# LAN_RJ45.net
KiCad netlist of a schematic drawn in Altium Designer
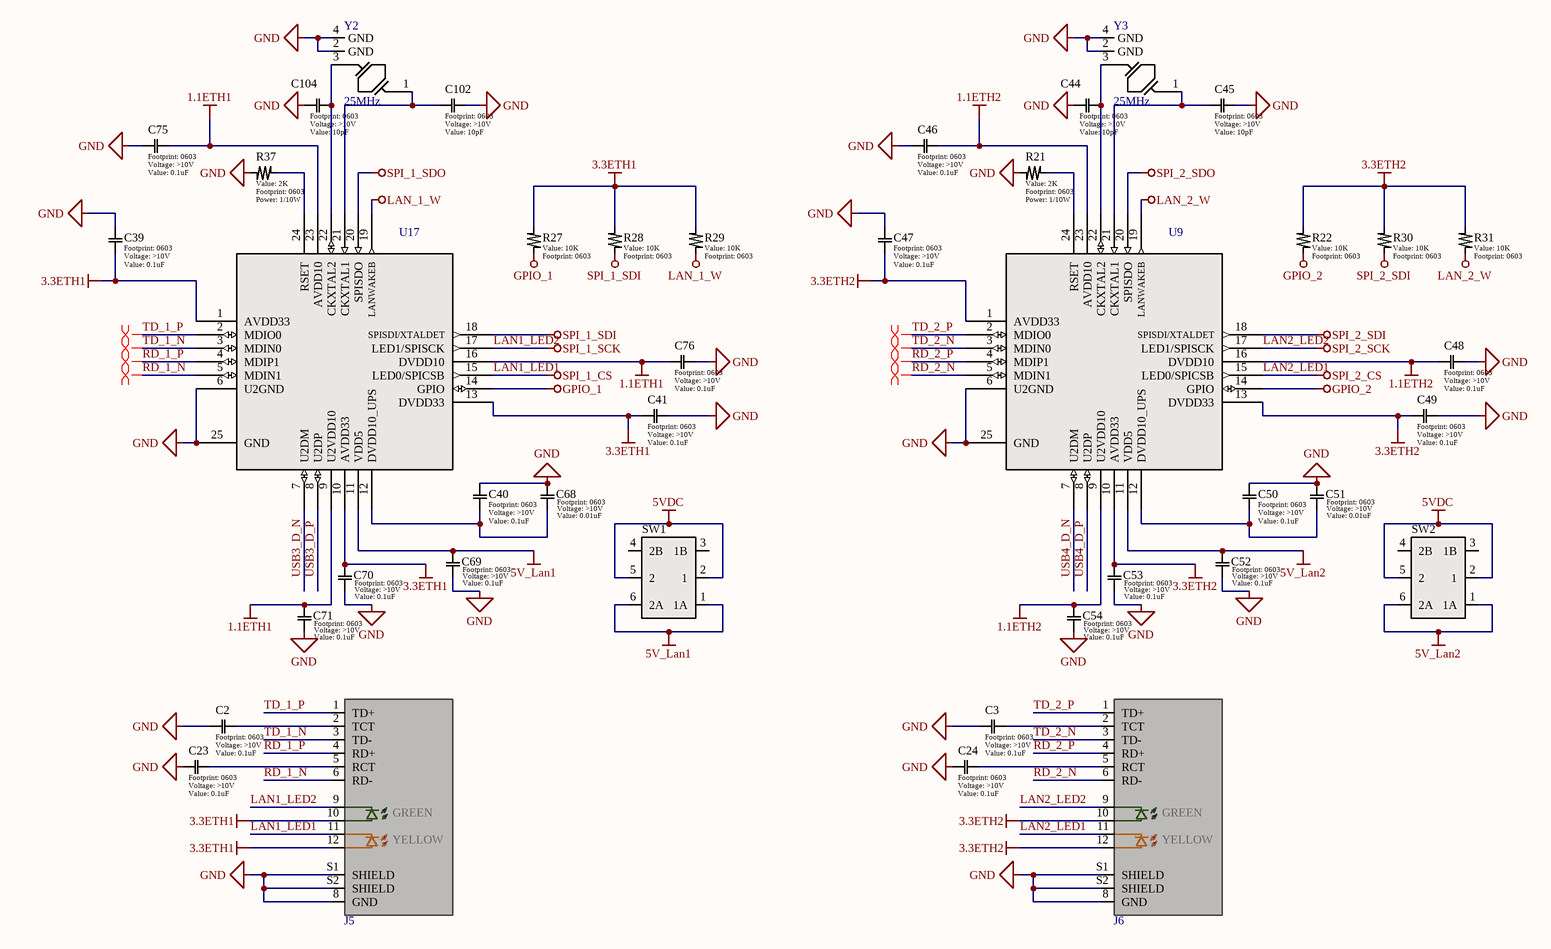
[diagram p0: LAN_RJ45.SchDoc]

(export (version "E")
  (design (tool "Eeschema 10.0.6"))
  (components
    (comp (ref "C2")
      (value "0.1uF")
      (footprint "0603")
      (fields
        (field (name "VOLTAGE") ">10V")
        (field (name "TOLERANCE") "10%")
        (field (name "Comment") "Generic Capacitor")
      )
      (libsource (lib "Capacitors") (part "Generic Capacitor"))
    )
    (comp (ref "C3")
      (value "0.1uF")
      (footprint "0603")
      (fields
        (field (name "VOLTAGE") ">10V")
        (field (name "TOLERANCE") "10%")
        (field (name "Comment") "Generic Capacitor")
      )
      (libsource (lib "Capacitors") (part "Generic Capacitor"))
    )
    (comp (ref "C23")
      (value "0.1uF")
      (footprint "0603")
      (fields
        (field (name "VOLTAGE") ">10V")
        (field (name "TOLERANCE") "10%")
        (field (name "Comment") "Generic Capacitor")
      )
      (libsource (lib "Capacitors") (part "Generic Capacitor"))
    )
    (comp (ref "C24")
      (value "0.1uF")
      (footprint "0603")
      (fields
        (field (name "VOLTAGE") ">10V")
        (field (name "TOLERANCE") "10%")
        (field (name "Comment") "Generic Capacitor")
      )
      (libsource (lib "Capacitors") (part "Generic Capacitor"))
    )
    (comp (ref "C39")
      (value "0.1uF")
      (footprint "0603")
      (fields
        (field (name "VOLTAGE") ">10V")
        (field (name "TOLERANCE") "10%")
        (field (name "Comment") "Generic Capacitor")
      )
      (libsource (lib "Capacitors") (part "Generic Capacitor"))
    )
    (comp (ref "C40")
      (value "0.1uF")
      (footprint "0603")
      (fields
        (field (name "VOLTAGE") ">10V")
        (field (name "TOLERANCE") "10%")
        (field (name "Comment") "Generic Capacitor")
      )
      (libsource (lib "Capacitors") (part "Generic Capacitor"))
    )
    (comp (ref "C41")
      (value "0.1uF")
      (footprint "0603")
      (fields
        (field (name "VOLTAGE") ">10V")
        (field (name "TOLERANCE") "10%")
        (field (name "Comment") "Generic Capacitor")
      )
      (libsource (lib "Capacitors") (part "Generic Capacitor"))
    )
    (comp (ref "C44")
      (value "10pF")
      (footprint "0603")
      (fields
        (field (name "VOLTAGE") ">10V")
        (field (name "TOLERANCE") "10%")
        (field (name "Comment") "Generic Capacitor")
      )
      (libsource (lib "Capacitors") (part "Generic Capacitor"))
    )
    (comp (ref "C45")
      (value "10pF")
      (footprint "0603")
      (fields
        (field (name "VOLTAGE") ">10V")
        (field (name "TOLERANCE") "10%")
        (field (name "Comment") "Generic Capacitor")
      )
      (libsource (lib "Capacitors") (part "Generic Capacitor"))
    )
    (comp (ref "C46")
      (value "0.1uF")
      (footprint "0603")
      (fields
        (field (name "VOLTAGE") ">10V")
        (field (name "TOLERANCE") "10%")
        (field (name "Comment") "Generic Capacitor")
      )
      (libsource (lib "Capacitors") (part "Generic Capacitor"))
    )
    (comp (ref "C47")
      (value "0.1uF")
      (footprint "0603")
      (fields
        (field (name "VOLTAGE") ">10V")
        (field (name "TOLERANCE") "10%")
        (field (name "Comment") "Generic Capacitor")
      )
      (libsource (lib "Capacitors") (part "Generic Capacitor"))
    )
    (comp (ref "C48")
      (value "0.1uF")
      (footprint "0603")
      (fields
        (field (name "VOLTAGE") ">10V")
        (field (name "TOLERANCE") "10%")
        (field (name "Comment") "Generic Capacitor")
      )
      (libsource (lib "Capacitors") (part "Generic Capacitor"))
    )
    (comp (ref "C49")
      (value "0.1uF")
      (footprint "0603")
      (fields
        (field (name "VOLTAGE") ">10V")
        (field (name "TOLERANCE") "10%")
        (field (name "Comment") "Generic Capacitor")
      )
      (libsource (lib "Capacitors") (part "Generic Capacitor"))
    )
    (comp (ref "C50")
      (value "0.1uF")
      (footprint "0603")
      (fields
        (field (name "VOLTAGE") ">10V")
        (field (name "TOLERANCE") "10%")
        (field (name "Comment") "Generic Capacitor")
      )
      (libsource (lib "Capacitors") (part "Generic Capacitor"))
    )
    (comp (ref "C51")
      (value "0.01uF")
      (footprint "0603")
      (fields
        (field (name "VOLTAGE") ">10V")
        (field (name "TOLERANCE") "10%")
        (field (name "Comment") "Generic Capacitor")
      )
      (libsource (lib "Capacitors") (part "Generic Capacitor"))
    )
    (comp (ref "C52")
      (value "0.1uF")
      (footprint "0603")
      (fields
        (field (name "VOLTAGE") ">10V")
        (field (name "TOLERANCE") "10%")
        (field (name "Comment") "Generic Capacitor")
      )
      (libsource (lib "Capacitors") (part "Generic Capacitor"))
    )
    (comp (ref "C53")
      (value "0.1uF")
      (footprint "0603")
      (fields
        (field (name "VOLTAGE") ">10V")
        (field (name "TOLERANCE") "10%")
        (field (name "Comment") "Generic Capacitor")
      )
      (libsource (lib "Capacitors") (part "Generic Capacitor"))
    )
    (comp (ref "C54")
      (value "0.1uF")
      (footprint "0603")
      (fields
        (field (name "VOLTAGE") ">10V")
        (field (name "TOLERANCE") "10%")
        (field (name "Comment") "Generic Capacitor")
      )
      (libsource (lib "Capacitors") (part "Generic Capacitor"))
    )
    (comp (ref "C68")
      (value "0.01uF")
      (footprint "0603")
      (fields
        (field (name "VOLTAGE") ">10V")
        (field (name "TOLERANCE") "10%")
        (field (name "Comment") "Generic Capacitor")
      )
      (libsource (lib "Capacitors") (part "Generic Capacitor"))
    )
    (comp (ref "C69")
      (value "0.1uF")
      (footprint "0603")
      (fields
        (field (name "VOLTAGE") ">10V")
        (field (name "TOLERANCE") "10%")
        (field (name "Comment") "Generic Capacitor")
      )
      (libsource (lib "Capacitors") (part "Generic Capacitor"))
    )
    (comp (ref "C70")
      (value "0.1uF")
      (footprint "0603")
      (fields
        (field (name "VOLTAGE") ">10V")
        (field (name "TOLERANCE") "10%")
        (field (name "Comment") "Generic Capacitor")
      )
      (libsource (lib "Capacitors") (part "Generic Capacitor"))
    )
    (comp (ref "C71")
      (value "0.1uF")
      (footprint "0603")
      (fields
        (field (name "VOLTAGE") ">10V")
        (field (name "TOLERANCE") "10%")
        (field (name "Comment") "Generic Capacitor")
      )
      (libsource (lib "Capacitors") (part "Generic Capacitor"))
    )
    (comp (ref "C75")
      (value "0.1uF")
      (footprint "0603")
      (fields
        (field (name "VOLTAGE") ">10V")
        (field (name "TOLERANCE") "10%")
        (field (name "Comment") "Generic Capacitor")
      )
      (libsource (lib "Capacitors") (part "Generic Capacitor"))
    )
    (comp (ref "C76")
      (value "0.1uF")
      (footprint "0603")
      (fields
        (field (name "VOLTAGE") ">10V")
        (field (name "TOLERANCE") "10%")
        (field (name "Comment") "Generic Capacitor")
      )
      (libsource (lib "Capacitors") (part "Generic Capacitor"))
    )
    (comp (ref "C102")
      (value "10pF")
      (footprint "0603")
      (fields
        (field (name "VOLTAGE") ">10V")
        (field (name "TOLERANCE") "10%")
        (field (name "Comment") "Generic Capacitor")
      )
      (libsource (lib "Capacitors") (part "Generic Capacitor"))
    )
    (comp (ref "C104")
      (value "10pF")
      (footprint "0603")
      (fields
        (field (name "VOLTAGE") ">10V")
        (field (name "TOLERANCE") "10%")
        (field (name "Comment") "Generic Capacitor")
      )
      (libsource (lib "Capacitors") (part "Generic Capacitor"))
    )
    (comp (ref "J5")
      (value "V-RJ45-100")
      (footprint "BEL_SI-46001-F")
      (description "Conn RJ-45 F 8 POS 2.54mm Solder ST Thru-Hole 12 Terminal 1 Port")
      (fields (field (name "MF") "Bel Magnetic Solutions") (field (name "MP") "SI-46001-F"))
      (libsource (lib "Connectors") (part "SI-46001-F"))
    )
    (comp (ref "J6")
      (value "V-RJ45-100")
      (footprint "BEL_SI-46001-F")
      (description "Conn RJ-45 F 8 POS 2.54mm Solder ST Thru-Hole 12 Terminal 1 Port")
      (fields (field (name "MF") "Bel Magnetic Solutions") (field (name "MP") "SI-46001-F"))
      (libsource (lib "Connectors") (part "SI-46001-F"))
    )
    (comp (ref "R21")
      (value "2K")
      (footprint "0603")
      (fields
        (field (name "TOLERANCE") "1%")
        (field (name "POWER") "1/10W")
        (field (name "Comment") "Generic Resistor")
      )
      (libsource (lib "Resistors") (part "Generic Resistor"))
    )
    (comp (ref "R22")
      (value "10K")
      (footprint "0603")
      (fields
        (field (name "TOLERANCE") "1%")
        (field (name "POWER") "1/10W")
        (field (name "Comment") "Generic Resistor")
      )
      (libsource (lib "Resistors") (part "Generic Resistor"))
    )
    (comp (ref "R27")
      (value "10K")
      (footprint "0603")
      (fields
        (field (name "TOLERANCE") "1%")
        (field (name "POWER") "1/10W")
        (field (name "Comment") "Generic Resistor")
      )
      (libsource (lib "Resistors") (part "Generic Resistor"))
    )
    (comp (ref "R28")
      (value "10K")
      (footprint "0603")
      (fields
        (field (name "TOLERANCE") "1%")
        (field (name "POWER") "1/10W")
        (field (name "Comment") "Generic Resistor")
      )
      (libsource (lib "Resistors") (part "Generic Resistor"))
    )
    (comp (ref "R29")
      (value "10K")
      (footprint "0603")
      (fields
        (field (name "TOLERANCE") "1%")
        (field (name "POWER") "1/10W")
        (field (name "Comment") "Generic Resistor")
      )
      (libsource (lib "Resistors") (part "Generic Resistor"))
    )
    (comp (ref "R30")
      (value "10K")
      (footprint "0603")
      (fields
        (field (name "TOLERANCE") "1%")
        (field (name "POWER") "1/10W")
        (field (name "Comment") "Generic Resistor")
      )
      (libsource (lib "Resistors") (part "Generic Resistor"))
    )
    (comp (ref "R31")
      (value "10K")
      (footprint "0603")
      (fields
        (field (name "TOLERANCE") "1%")
        (field (name "POWER") "1/10W")
        (field (name "Comment") "Generic Resistor")
      )
      (libsource (lib "Resistors") (part "Generic Resistor"))
    )
    (comp (ref "R37")
      (value "2K")
      (footprint "0603")
      (fields
        (field (name "TOLERANCE") "1%")
        (field (name "POWER") "1/10W")
        (field (name "Comment") "Generic Resistor")
      )
      (libsource (lib "Resistors") (part "Generic Resistor"))
    )
    (comp (ref "SW1")
      (value "~")
      (footprint "SMD-DPDT-SW")
      (description "Brick nogging DPDT Black SMD Slide Switch")
      (libsource (lib "Switches") (part "MS-22D17-G2"))
    )
    (comp (ref "SW2")
      (value "~")
      (footprint "SMD-DPDT-SW")
      (description "Brick nogging DPDT Black SMD Slide Switch")
      (libsource (lib "Switches") (part "MS-22D17-G2"))
    )
    (comp (ref "U9")
      (value "10/100 USB LAN")
      (footprint "RTL8152B-VB-CG")
      (libsource (lib "Misc ICs") (part "RTL8152B-VB-CG"))
    )
    (comp (ref "U17")
      (value "10/100 USB LAN")
      (footprint "RTL8152B-VB-CG")
      (libsource (lib "Misc ICs") (part "RTL8152B-VB-CG"))
    )
    (comp (ref "Y2")
      (value "25MHz")
      (footprint "SMD3225-4P")
      (description "25 MHz ±30ppm Crystal 10pF 60 Ohms 4-SMD, No Lead\r\nSMD3225-4P")
      (fields
        (field (name "MANUFACTURER") "Abracon")
        (field (name "MANUFACTURER PART NUMBER") "ABM8G-25.000MHZ-B4Y-T")
      )
      (libsource (lib "Clock ICs") (part "ABM8G-25.000MHZ-B4Y-T"))
    )
    (comp (ref "Y3")
      (value "25MHz")
      (footprint "SMD3225-4P")
      (description "25 MHz ±30ppm Crystal 10pF 60 Ohms 4-SMD, No Lead\r\nSMD3225-4P")
      (fields
        (field (name "MANUFACTURER") "Abracon")
        (field (name "MANUFACTURER PART NUMBER") "ABM8G-25.000MHZ-B4Y-T")
      )
      (libsource (lib "Clock ICs") (part "ABM8G-25.000MHZ-B4Y-T"))
    )
  )
  (nets
    (net (code "1") (name "/RD_1_N") (class "Default")
      (node (ref "J5") (pin "6") (pinfunction "RD-_6") (pintype "passive"))
      (node (ref "U17") (pin "5") (pinfunction "MDIN1_5") (pintype "bidirectional"))
    )
    (net (code "2") (name "/RD_1_P") (class "Default")
      (node (ref "J5") (pin "4") (pinfunction "RD+_4") (pintype "passive"))
      (node (ref "U17") (pin "4") (pinfunction "MDIP1_4") (pintype "bidirectional"))
    )
    (net (code "3") (name "/RD_2_N") (class "Default")
      (node (ref "J6") (pin "6") (pinfunction "RD-_6") (pintype "passive"))
      (node (ref "U9") (pin "5") (pinfunction "MDIN1_5") (pintype "bidirectional"))
    )
    (net (code "4") (name "/RD_2_P") (class "Default")
      (node (ref "J6") (pin "4") (pinfunction "RD+_4") (pintype "passive"))
      (node (ref "U9") (pin "4") (pinfunction "MDIP1_4") (pintype "bidirectional"))
    )
    (net (code "5") (name "/TD_1_N") (class "Default")
      (node (ref "J5") (pin "3") (pinfunction "TD-_3") (pintype "passive"))
      (node (ref "U17") (pin "3") (pinfunction "MDIN0_3") (pintype "bidirectional"))
    )
    (net (code "6") (name "/TD_1_P") (class "Default")
      (node (ref "J5") (pin "1") (pinfunction "TD+_1") (pintype "passive"))
      (node (ref "U17") (pin "2") (pinfunction "MDIO0_2") (pintype "bidirectional"))
    )
    (net (code "7") (name "/TD_2_N") (class "Default")
      (node (ref "J6") (pin "3") (pinfunction "TD-_3") (pintype "passive"))
      (node (ref "U9") (pin "3") (pinfunction "MDIN0_3") (pintype "bidirectional"))
    )
    (net (code "8") (name "/TD_2_P") (class "Default")
      (node (ref "J6") (pin "1") (pinfunction "TD+_1") (pintype "passive"))
      (node (ref "U9") (pin "2") (pinfunction "MDIO0_2") (pintype "bidirectional"))
    )
    (net (code "9") (name "/USB3_D_N") (class "Default")
      (node (ref "U17") (pin "7") (pinfunction "U2DM_7") (pintype "bidirectional"))
    )
    (net (code "10") (name "/USB3_D_P") (class "Default")
      (node (ref "U17") (pin "8") (pinfunction "U2DP_8") (pintype "bidirectional"))
    )
    (net (code "11") (name "/USB4_D_N") (class "Default")
      (node (ref "U9") (pin "7") (pinfunction "U2DM_7") (pintype "bidirectional"))
    )
    (net (code "12") (name "/USB4_D_P") (class "Default")
      (node (ref "U9") (pin "8") (pinfunction "U2DP_8") (pintype "bidirectional"))
    )
    (net (code "13") (name "1.1ETH1") (class "Default")
      (node (ref "C71") (pin "1") (pinfunction "1_1") (pintype "passive"))
      (node (ref "C75") (pin "1") (pinfunction "1_1") (pintype "passive"))
      (node (ref "C76") (pin "2") (pinfunction "2_2") (pintype "passive"))
      (node (ref "U17") (pin "16") (pinfunction "DVDD10_16") (pintype "power_in"))
      (node (ref "U17") (pin "23") (pinfunction "AVDD10_23") (pintype "power_in"))
      (node (ref "U17") (pin "9") (pinfunction "U2VDD10_9") (pintype "power_in"))
    )
    (net (code "14") (name "1.1ETH2") (class "Default")
      (node (ref "C46") (pin "1") (pinfunction "1_1") (pintype "passive"))
      (node (ref "C48") (pin "2") (pinfunction "2_2") (pintype "passive"))
      (node (ref "C54") (pin "1") (pinfunction "1_1") (pintype "passive"))
      (node (ref "U9") (pin "16") (pinfunction "DVDD10_16") (pintype "power_in"))
      (node (ref "U9") (pin "23") (pinfunction "AVDD10_23") (pintype "power_in"))
      (node (ref "U9") (pin "9") (pinfunction "U2VDD10_9") (pintype "power_in"))
    )
    (net (code "15") (name "3.3ETH1") (class "Default")
      (node (ref "C39") (pin "1") (pinfunction "1_1") (pintype "passive"))
      (node (ref "C41") (pin "2") (pinfunction "2_2") (pintype "passive"))
      (node (ref "C70") (pin "1") (pinfunction "1_1") (pintype "passive"))
      (node (ref "J5") (pin "10") (pinfunction "GA_10") (pintype "passive"))
      (node (ref "J5") (pin "12") (pinfunction "YA_12") (pintype "passive"))
      (node (ref "R27") (pin "1") (pinfunction "1_1") (pintype "passive"))
      (node (ref "R28") (pin "1") (pinfunction "1_1") (pintype "passive"))
      (node (ref "R29") (pin "1") (pinfunction "1_1") (pintype "passive"))
      (node (ref "U17") (pin "1") (pinfunction "AVDD33_1") (pintype "power_in"))
      (node (ref "U17") (pin "10") (pinfunction "AVDD33_10") (pintype "power_in"))
      (node (ref "U17") (pin "13") (pinfunction "DVDD33_13") (pintype "power_in"))
    )
    (net (code "16") (name "3.3ETH2") (class "Default")
      (node (ref "C47") (pin "1") (pinfunction "1_1") (pintype "passive"))
      (node (ref "C49") (pin "2") (pinfunction "2_2") (pintype "passive"))
      (node (ref "C53") (pin "1") (pinfunction "1_1") (pintype "passive"))
      (node (ref "J6") (pin "10") (pinfunction "GA_10") (pintype "passive"))
      (node (ref "J6") (pin "12") (pinfunction "YA_12") (pintype "passive"))
      (node (ref "R22") (pin "1") (pinfunction "1_1") (pintype "passive"))
      (node (ref "R30") (pin "1") (pinfunction "1_1") (pintype "passive"))
      (node (ref "R31") (pin "1") (pinfunction "1_1") (pintype "passive"))
      (node (ref "U9") (pin "1") (pinfunction "AVDD33_1") (pintype "power_in"))
      (node (ref "U9") (pin "10") (pinfunction "AVDD33_10") (pintype "power_in"))
      (node (ref "U9") (pin "13") (pinfunction "DVDD33_13") (pintype "power_in"))
    )
    (net (code "17") (name "5VDC") (class "Default")
      (node (ref "SW1") (pin "2") (pinfunction "1_2") (pintype "passive"))
      (node (ref "SW1") (pin "5") (pinfunction "2_5") (pintype "passive"))
      (node (ref "SW2") (pin "2") (pinfunction "1_2") (pintype "passive"))
      (node (ref "SW2") (pin "5") (pinfunction "2_5") (pintype "passive"))
    )
    (net (code "18") (name "5V_Lan1") (class "Default")
      (node (ref "C69") (pin "1") (pinfunction "1_1") (pintype "passive"))
      (node (ref "SW1") (pin "1") (pinfunction "1A_1") (pintype "passive"))
      (node (ref "SW1") (pin "6") (pinfunction "2A_6") (pintype "passive"))
      (node (ref "U17") (pin "11") (pinfunction "VDD5_11") (pintype "power_in"))
    )
    (net (code "19") (name "5V_Lan2") (class "Default")
      (node (ref "C52") (pin "1") (pinfunction "1_1") (pintype "passive"))
      (node (ref "SW2") (pin "1") (pinfunction "1A_1") (pintype "passive"))
      (node (ref "SW2") (pin "6") (pinfunction "2A_6") (pintype "passive"))
      (node (ref "U9") (pin "11") (pinfunction "VDD5_11") (pintype "power_in"))
    )
    (net (code "20") (name "GND") (class "Default")
      (node (ref "C102") (pin "1") (pinfunction "1_1") (pintype "passive"))
      (node (ref "C104") (pin "2") (pinfunction "2_2") (pintype "passive"))
      (node (ref "C2") (pin "1") (pinfunction "1_1") (pintype "passive"))
      (node (ref "C23") (pin "1") (pinfunction "1_1") (pintype "passive"))
      (node (ref "C24") (pin "1") (pinfunction "1_1") (pintype "passive"))
      (node (ref "C3") (pin "1") (pinfunction "1_1") (pintype "passive"))
      (node (ref "C39") (pin "2") (pinfunction "2_2") (pintype "passive"))
      (node (ref "C40") (pin "1") (pinfunction "1_1") (pintype "passive"))
      (node (ref "C41") (pin "1") (pinfunction "1_1") (pintype "passive"))
      (node (ref "C44") (pin "2") (pinfunction "2_2") (pintype "passive"))
      (node (ref "C45") (pin "1") (pinfunction "1_1") (pintype "passive"))
      (node (ref "C46") (pin "2") (pinfunction "2_2") (pintype "passive"))
      (node (ref "C47") (pin "2") (pinfunction "2_2") (pintype "passive"))
      (node (ref "C48") (pin "1") (pinfunction "1_1") (pintype "passive"))
      (node (ref "C49") (pin "1") (pinfunction "1_1") (pintype "passive"))
      (node (ref "C50") (pin "1") (pinfunction "1_1") (pintype "passive"))
      (node (ref "C51") (pin "1") (pinfunction "1_1") (pintype "passive"))
      (node (ref "C52") (pin "2") (pinfunction "2_2") (pintype "passive"))
      (node (ref "C53") (pin "2") (pinfunction "2_2") (pintype "passive"))
      (node (ref "C54") (pin "2") (pinfunction "2_2") (pintype "passive"))
      (node (ref "C68") (pin "1") (pinfunction "1_1") (pintype "passive"))
      (node (ref "C69") (pin "2") (pinfunction "2_2") (pintype "passive"))
      (node (ref "C70") (pin "2") (pinfunction "2_2") (pintype "passive"))
      (node (ref "C71") (pin "2") (pinfunction "2_2") (pintype "passive"))
      (node (ref "C75") (pin "2") (pinfunction "2_2") (pintype "passive"))
      (node (ref "C76") (pin "1") (pinfunction "1_1") (pintype "passive"))
      (node (ref "J5") (pin "8") (pinfunction "GND_8") (pintype "power_in"))
      (node (ref "J5") (pin "S1") (pinfunction "SHIELD_S1") (pintype "passive"))
      (node (ref "J5") (pin "S2") (pinfunction "SHIELD_S2") (pintype "passive"))
      (node (ref "J6") (pin "8") (pinfunction "GND_8") (pintype "power_in"))
      (node (ref "J6") (pin "S1") (pinfunction "SHIELD_S1") (pintype "passive"))
      (node (ref "J6") (pin "S2") (pinfunction "SHIELD_S2") (pintype "passive"))
      (node (ref "R21") (pin "1") (pinfunction "1_1") (pintype "passive"))
      (node (ref "R37") (pin "1") (pinfunction "1_1") (pintype "passive"))
      (node (ref "U17") (pin "25") (pinfunction "GND_25") (pintype "passive"))
      (node (ref "U17") (pin "6") (pinfunction "U2GND_6") (pintype "passive"))
      (node (ref "U9") (pin "25") (pinfunction "GND_25") (pintype "passive"))
      (node (ref "U9") (pin "6") (pinfunction "U2GND_6") (pintype "passive"))
      (node (ref "Y2") (pin "2") (pinfunction "GND_2") (pintype "passive"))
      (node (ref "Y2") (pin "4") (pinfunction "GND_4") (pintype "passive"))
      (node (ref "Y3") (pin "2") (pinfunction "GND_2") (pintype "passive"))
      (node (ref "Y3") (pin "4") (pinfunction "GND_4") (pintype "passive"))
    )
    (net (code "21") (name "GPIO_1") (class "Default")
      (node (ref "R27") (pin "2") (pinfunction "2_2") (pintype "passive"))
      (node (ref "U17") (pin "14") (pinfunction "GPIO_14") (pintype "bidirectional"))
    )
    (net (code "22") (name "GPIO_2") (class "Default")
      (node (ref "R22") (pin "2") (pinfunction "2_2") (pintype "passive"))
      (node (ref "U9") (pin "14") (pinfunction "GPIO_14") (pintype "bidirectional"))
    )
    (net (code "23") (name "LAN_1_W") (class "Default")
      (node (ref "R29") (pin "2") (pinfunction "2_2") (pintype "passive"))
      (node (ref "U17") (pin "19") (pinfunction "LANWAKEB_19") (pintype "output"))
    )
    (net (code "24") (name "LAN_2_W") (class "Default")
      (node (ref "R31") (pin "2") (pinfunction "2_2") (pintype "passive"))
      (node (ref "U9") (pin "19") (pinfunction "LANWAKEB_19") (pintype "output"))
    )
    (net (code "25") (name "Net-(J5-RCT)") (class "Default")
      (node (ref "C23") (pin "2") (pinfunction "2_2") (pintype "passive"))
      (node (ref "J5") (pin "5") (pinfunction "RCT_5") (pintype "passive"))
    )
    (net (code "26") (name "Net-(J5-TCT)") (class "Default")
      (node (ref "C2") (pin "2") (pinfunction "2_2") (pintype "passive"))
      (node (ref "J5") (pin "2") (pinfunction "TCT_2") (pintype "passive"))
    )
    (net (code "27") (name "Net-(J6-RCT)") (class "Default")
      (node (ref "C24") (pin "2") (pinfunction "2_2") (pintype "passive"))
      (node (ref "J6") (pin "5") (pinfunction "RCT_5") (pintype "passive"))
    )
    (net (code "28") (name "Net-(J6-TCT)") (class "Default")
      (node (ref "C3") (pin "2") (pinfunction "2_2") (pintype "passive"))
      (node (ref "J6") (pin "2") (pinfunction "TCT_2") (pintype "passive"))
    )
    (net (code "29") (name "Net-(U9-CKXTAL1)") (class "Default")
      (node (ref "C45") (pin "2") (pinfunction "2_2") (pintype "passive"))
      (node (ref "U9") (pin "21") (pinfunction "CKXTAL1_21") (pintype "input"))
      (node (ref "Y3") (pin "1") (pinfunction "1_1") (pintype "passive"))
    )
    (net (code "30") (name "Net-(U9-CKXTAL2)") (class "Default")
      (node (ref "C44") (pin "1") (pinfunction "1_1") (pintype "passive"))
      (node (ref "U9") (pin "22") (pinfunction "CKXTAL2_22") (pintype "bidirectional"))
      (node (ref "Y3") (pin "3") (pinfunction "3_3") (pintype "passive"))
    )
    (net (code "31") (name "Net-(U9-DVDD10_UPS)") (class "Default")
      (node (ref "C50") (pin "2") (pinfunction "2_2") (pintype "passive"))
      (node (ref "C51") (pin "2") (pinfunction "2_2") (pintype "passive"))
      (node (ref "U9") (pin "12") (pinfunction "DVDD10_UPS_12") (pintype "power_in"))
    )
    (net (code "32") (name "Net-(U9-RSET)") (class "Default")
      (node (ref "R21") (pin "2") (pinfunction "2_2") (pintype "passive"))
      (node (ref "U9") (pin "24") (pinfunction "RSET_24") (pintype "power_in"))
    )
    (net (code "33") (name "Net-(U17-CKXTAL1)") (class "Default")
      (node (ref "C102") (pin "2") (pinfunction "2_2") (pintype "passive"))
      (node (ref "U17") (pin "21") (pinfunction "CKXTAL1_21") (pintype "input"))
      (node (ref "Y2") (pin "1") (pinfunction "1_1") (pintype "passive"))
    )
    (net (code "34") (name "Net-(U17-CKXTAL2)") (class "Default")
      (node (ref "C104") (pin "1") (pinfunction "1_1") (pintype "passive"))
      (node (ref "U17") (pin "22") (pinfunction "CKXTAL2_22") (pintype "bidirectional"))
      (node (ref "Y2") (pin "3") (pinfunction "3_3") (pintype "passive"))
    )
    (net (code "35") (name "Net-(U17-DVDD10_UPS)") (class "Default")
      (node (ref "C40") (pin "2") (pinfunction "2_2") (pintype "passive"))
      (node (ref "C68") (pin "2") (pinfunction "2_2") (pintype "passive"))
      (node (ref "U17") (pin "12") (pinfunction "DVDD10_UPS_12") (pintype "power_in"))
    )
    (net (code "36") (name "Net-(U17-RSET)") (class "Default")
      (node (ref "R37") (pin "2") (pinfunction "2_2") (pintype "passive"))
      (node (ref "U17") (pin "24") (pinfunction "RSET_24") (pintype "power_in"))
    )
    (net (code "37") (name "SPI_1_CS") (class "Default")
      (node (ref "J5") (pin "11") (pinfunction "YK_11") (pintype "passive"))
      (node (ref "U17") (pin "15") (pinfunction "LED0/SPICSB_15") (pintype "output"))
    )
    (net (code "38") (name "SPI_1_SCK") (class "Default")
      (node (ref "J5") (pin "9") (pinfunction "GK_9") (pintype "passive"))
      (node (ref "U17") (pin "17") (pinfunction "LED1/SPISCK_17") (pintype "output"))
    )
    (net (code "39") (name "SPI_1_SDI") (class "Default")
      (node (ref "R28") (pin "2") (pinfunction "2_2") (pintype "passive"))
      (node (ref "U17") (pin "18") (pinfunction "SPISDI/XTALDET_18") (pintype "output"))
    )
    (net (code "40") (name "SPI_1_SDO") (class "Default")
      (node (ref "U17") (pin "20") (pinfunction "SPISDO_20") (pintype "input"))
    )
    (net (code "41") (name "SPI_2_CS") (class "Default")
      (node (ref "J6") (pin "11") (pinfunction "YK_11") (pintype "passive"))
      (node (ref "U9") (pin "15") (pinfunction "LED0/SPICSB_15") (pintype "output"))
    )
    (net (code "42") (name "SPI_2_SCK") (class "Default")
      (node (ref "J6") (pin "9") (pinfunction "GK_9") (pintype "passive"))
      (node (ref "U9") (pin "17") (pinfunction "LED1/SPISCK_17") (pintype "output"))
    )
    (net (code "43") (name "SPI_2_SDI") (class "Default")
      (node (ref "R30") (pin "2") (pinfunction "2_2") (pintype "passive"))
      (node (ref "U9") (pin "18") (pinfunction "SPISDI/XTALDET_18") (pintype "output"))
    )
    (net (code "44") (name "SPI_2_SDO") (class "Default")
      (node (ref "U9") (pin "20") (pinfunction "SPISDO_20") (pintype "input"))
    )
    (net (code "45") (name "unconnected-(SW1-1B-Pad3)") (class "Default")
      (node (ref "SW1") (pin "3") (pinfunction "1B_3") (pintype "passive"))
    )
    (net (code "46") (name "unconnected-(SW1-2B-Pad4)") (class "Default")
      (node (ref "SW1") (pin "4") (pinfunction "2B_4") (pintype "passive"))
    )
    (net (code "47") (name "unconnected-(SW2-1B-Pad3)") (class "Default")
      (node (ref "SW2") (pin "3") (pinfunction "1B_3") (pintype "passive"))
    )
    (net (code "48") (name "unconnected-(SW2-2B-Pad4)") (class "Default")
      (node (ref "SW2") (pin "4") (pinfunction "2B_4") (pintype "passive"))
    )
  )
)
